# espism-v3.net
KiCad netlist of a schematic drawn in EAGLE
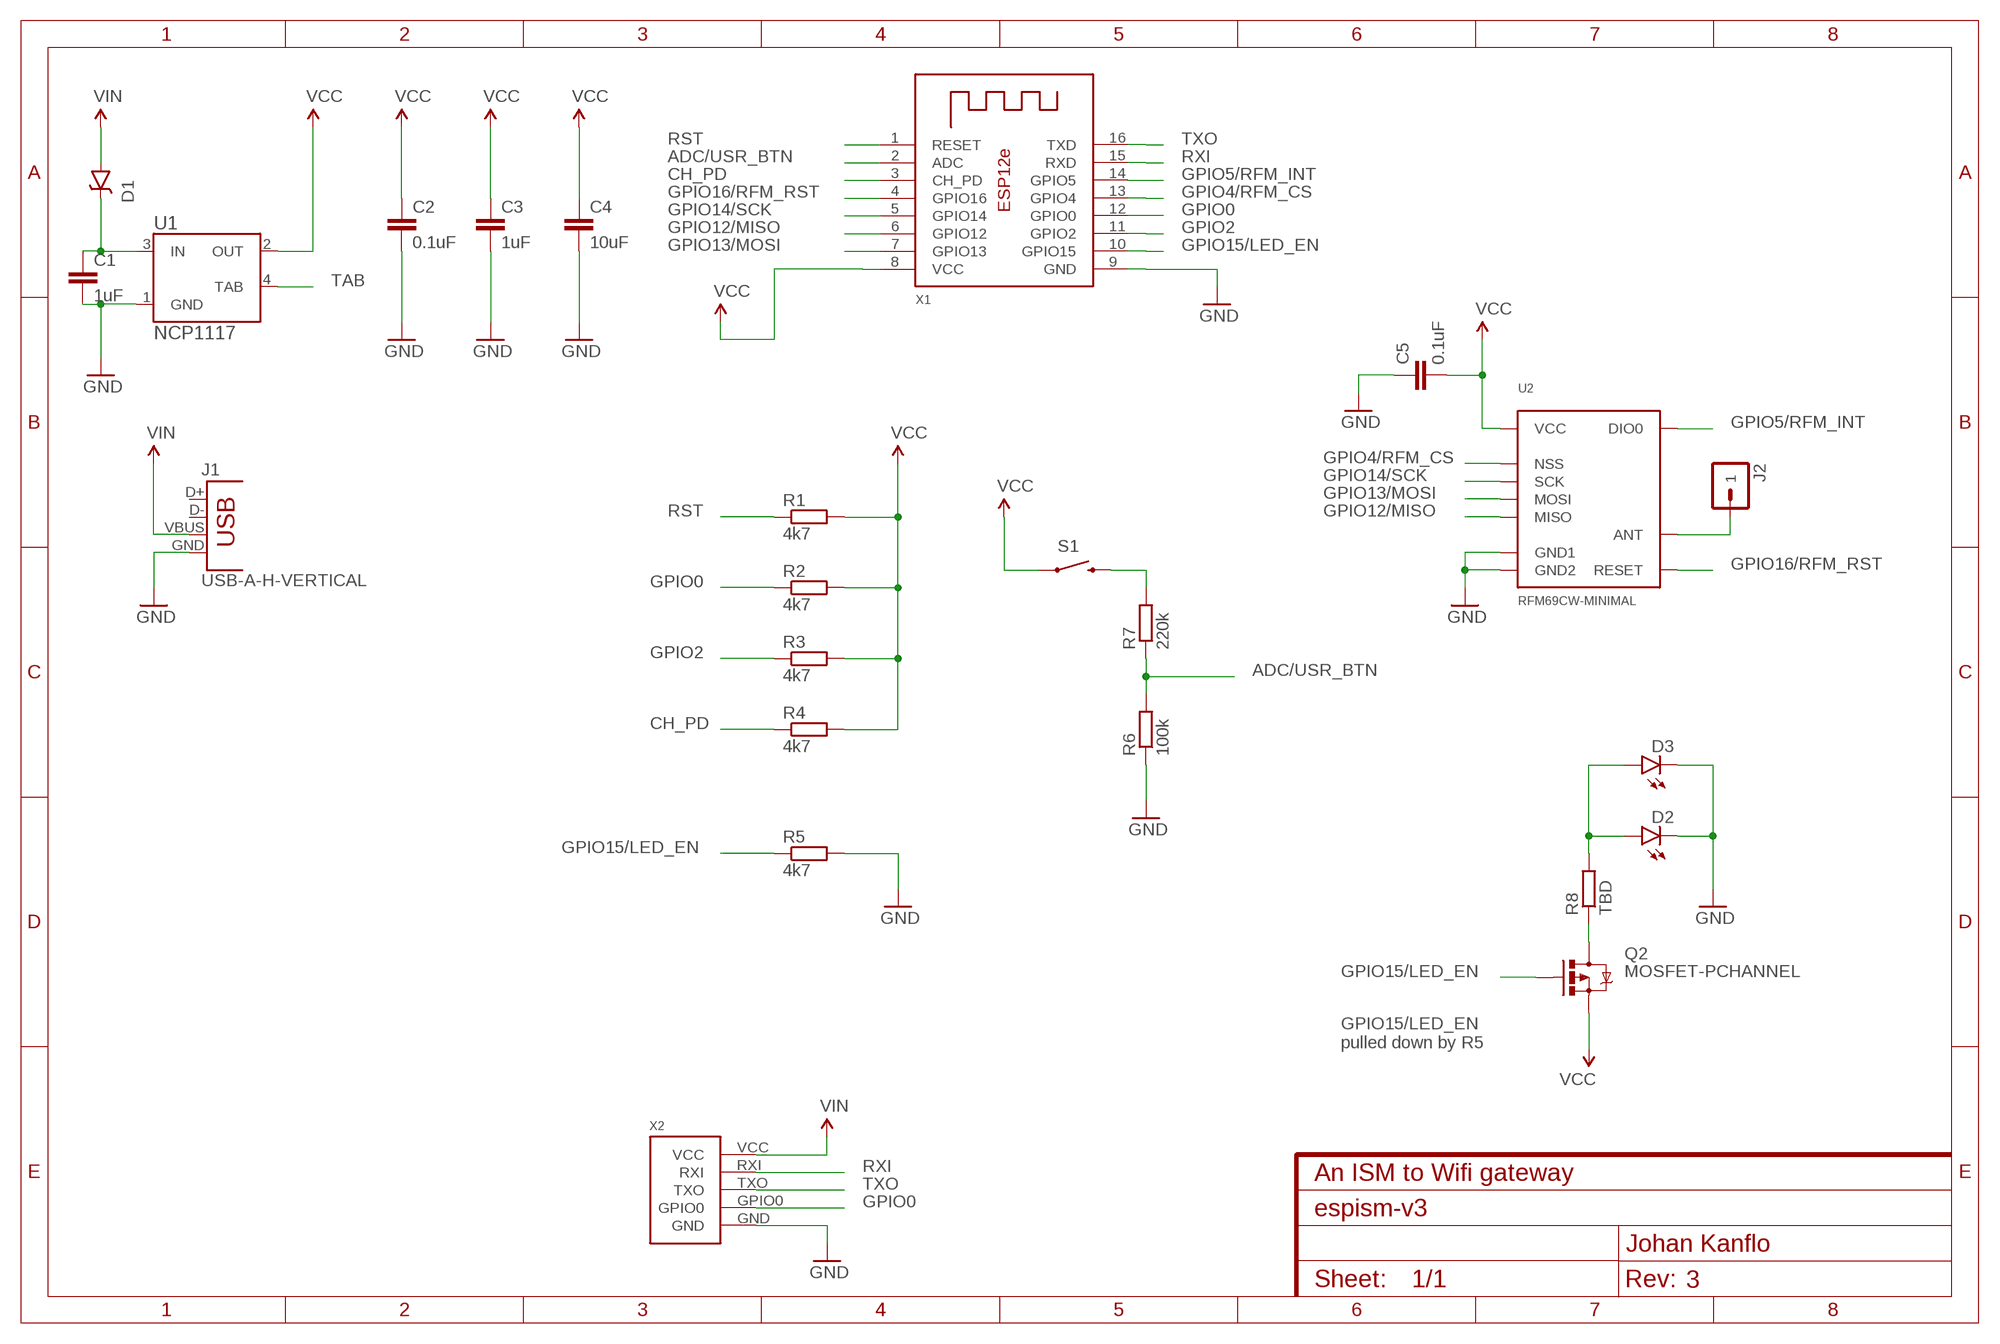
[diagram p0: schematic, sheet 1]

(export (version "E")
  (design (tool "Eeschema 10.0.6"))
  (components
    (comp (ref "C1")
      (value "1uF")
      (footprint "eagle-import:0603-CAP")
      (libsource (lib "eagle-import") (part "CAP0603-CAP"))
    )
    (comp (ref "C2")
      (value "0.1uF")
      (footprint "eagle-import:0603-CAP")
      (libsource (lib "eagle-import") (part "CAP0603-CAP"))
    )
    (comp (ref "C3")
      (value "1uF")
      (footprint "eagle-import:0603-CAP")
      (libsource (lib "eagle-import") (part "CAP0603-CAP"))
    )
    (comp (ref "C4")
      (value "10uF")
      (footprint "eagle-import:0603-CAP")
      (libsource (lib "eagle-import") (part "CAP0603-CAP"))
    )
    (comp (ref "C5")
      (value "0.1uF")
      (footprint "eagle-import:0603-CAP")
      (libsource (lib "eagle-import") (part "CAP0603-CAP"))
    )
    (comp (ref "D1")
      (value "DIODE-SCHOTTKYSOD-123FL")
      (footprint "eagle-import:SOD-123FL")
      (libsource (lib "eagle-import") (part "DIODE-SCHOTTKYSOD-123FL"))
    )
    (comp (ref "D2")
      (value "LED0603")
      (footprint "eagle-import:LED-0603")
      (libsource (lib "eagle-import") (part "LED0603"))
    )
    (comp (ref "D3")
      (value "LED0603")
      (footprint "eagle-import:LED-0603")
      (libsource (lib "eagle-import") (part "LED0603"))
    )
    (comp (ref "J1")
      (value "USB-A-H-VERTICAL")
      (footprint "eagle-import:USB-A-H-VERTICAL")
      (libsource (lib "eagle-import") (part "USB-A-H-VERTICAL"))
    )
    (comp (ref "J2")
      (value "M01-ANTENNA")
      (footprint "eagle-import:1X01-ANTENNA")
      (libsource (lib "eagle-import") (part "M01-ANTENNA"))
    )
    (comp (ref "Q2")
      (value "MOSFET-PCHANNEL")
      (footprint "eagle-import:SOT23-3")
      (libsource (lib "eagle-import") (part "MOSFET-PCHANNEL"))
    )
    (comp (ref "R1")
      (value "4k7")
      (footprint "eagle-import:R0603")
      (libsource (lib "eagle-import") (part "R-EU_R0603"))
    )
    (comp (ref "R2")
      (value "4k7")
      (footprint "eagle-import:R0603")
      (libsource (lib "eagle-import") (part "R-EU_R0603"))
    )
    (comp (ref "R3")
      (value "4k7")
      (footprint "eagle-import:R0603")
      (libsource (lib "eagle-import") (part "R-EU_R0603"))
    )
    (comp (ref "R4")
      (value "4k7")
      (footprint "eagle-import:R0603")
      (libsource (lib "eagle-import") (part "R-EU_R0603"))
    )
    (comp (ref "R5")
      (value "4k7")
      (footprint "eagle-import:R0603")
      (libsource (lib "eagle-import") (part "R-EU_R0603"))
    )
    (comp (ref "R6")
      (value "100k")
      (footprint "eagle-import:R0603")
      (libsource (lib "eagle-import") (part "R-EU_R0603"))
    )
    (comp (ref "R7")
      (value "220k")
      (footprint "eagle-import:R0603")
      (libsource (lib "eagle-import") (part "R-EU_R0603"))
    )
    (comp (ref "R8")
      (value "TBD")
      (footprint "eagle-import:R0603")
      (libsource (lib "eagle-import") (part "R-EU_R0603"))
    )
    (comp (ref "S1")
      (value "SWITCH-MOMENTARY-2SMD-1101NE")
      (footprint "eagle-import:TACTILE-SWITCH-1101NE")
      (libsource (lib "eagle-import") (part "SWITCH-MOMENTARY-2SMD-1101NE"))
    )
    (comp (ref "U1")
      (value "NCP1117")
      (footprint "eagle-import:SOT223")
      (libsource (lib "eagle-import") (part "NCP1117"))
    )
    (comp (ref "U2")
      (value "RFM69CW-MINIMAL")
      (footprint "eagle-import:RFM69CW-MINIMAL")
      (libsource (lib "eagle-import") (part "RFM69CW-MINIMAL"))
    )
    (comp (ref "X1")
      (value "ESP-12E")
      (footprint "eagle-import:ESP-12E")
      (libsource (lib "eagle-import") (part "ESP-12E"))
    )
    (comp (ref "X2")
      (value "ESPROGESPROG-DEVICE")
      (footprint "eagle-import:ESPROG")
      (libsource (lib "eagle-import") (part "ESPROGESPROG-DEVICE"))
    )
  )
  (nets
    (net (code "1") (name "/ADC{slash}USR_BTN") (class "Default")
      (node (ref "R6") (pin "2") (pinfunction "2_2") (pintype "passive"))
      (node (ref "R7") (pin "1") (pinfunction "1_1") (pintype "passive"))
      (node (ref "X1") (pin "2") (pinfunction "ADC_2") (pintype "passive"))
    )
    (net (code "2") (name "/CH_PD") (class "Default")
      (node (ref "R4") (pin "1") (pinfunction "1_1") (pintype "passive"))
      (node (ref "X1") (pin "3") (pinfunction "CH_PD_3") (pintype "input"))
    )
    (net (code "3") (name "/GPIO0") (class "Default")
      (node (ref "R2") (pin "1") (pinfunction "1_1") (pintype "passive"))
      (node (ref "X1") (pin "12") (pinfunction "GPIO0_12") (pintype "bidirectional"))
      (node (ref "X2") (pin "GPIO0") (pinfunction "GPIO0_GPIO0") (pintype "bidirectional"))
    )
    (net (code "4") (name "/GPIO2") (class "Default")
      (node (ref "R3") (pin "1") (pinfunction "1_1") (pintype "passive"))
      (node (ref "X1") (pin "11") (pinfunction "GPIO2_11") (pintype "bidirectional"))
    )
    (net (code "5") (name "/GPIO4{slash}RFM_CS") (class "Default")
      (node (ref "U2") (pin "NSS") (pinfunction "NSS_NSS") (pintype "input"))
      (node (ref "X1") (pin "13") (pinfunction "GPIO4_13") (pintype "bidirectional"))
    )
    (net (code "6") (name "/GPIO5{slash}RFM_INT") (class "Default")
      (node (ref "U2") (pin "DIO0") (pinfunction "DIO0_DIO0") (pintype "open_collector"))
      (node (ref "X1") (pin "14") (pinfunction "GPIO5_14") (pintype "bidirectional"))
    )
    (net (code "7") (name "/GPIO12{slash}MISO") (class "Default")
      (node (ref "U2") (pin "MISO") (pinfunction "MISO_MISO") (pintype "output"))
      (node (ref "X1") (pin "6") (pinfunction "GPIO12_6") (pintype "bidirectional"))
    )
    (net (code "8") (name "/GPIO13{slash}MOSI") (class "Default")
      (node (ref "U2") (pin "MOSI") (pinfunction "MOSI_MOSI") (pintype "input"))
      (node (ref "X1") (pin "7") (pinfunction "GPIO13_7") (pintype "bidirectional"))
    )
    (net (code "9") (name "/GPIO14{slash}SCK") (class "Default")
      (node (ref "U2") (pin "SCK") (pinfunction "SCK_SCK") (pintype "input"))
      (node (ref "X1") (pin "5") (pinfunction "GPIO14_5") (pintype "bidirectional"))
    )
    (net (code "10") (name "/GPIO15{slash}LED_EN") (class "Default")
      (node (ref "Q2") (pin "1") (pinfunction "G_1") (pintype "passive"))
      (node (ref "R5") (pin "1") (pinfunction "1_1") (pintype "passive"))
      (node (ref "X1") (pin "10") (pinfunction "GPIO15_10") (pintype "bidirectional"))
    )
    (net (code "11") (name "/GPIO16{slash}RFM_RST") (class "Default")
      (node (ref "U2") (pin "RESET") (pinfunction "RESET_RESET") (pintype "bidirectional"))
      (node (ref "X1") (pin "4") (pinfunction "GPIO16_4") (pintype "bidirectional"))
    )
    (net (code "12") (name "/RST") (class "Default")
      (node (ref "R1") (pin "1") (pinfunction "1_1") (pintype "passive"))
      (node (ref "X1") (pin "1") (pinfunction "RESET_1") (pintype "input"))
    )
    (net (code "13") (name "/RXI") (class "Default")
      (node (ref "X1") (pin "15") (pinfunction "RXD_15") (pintype "input"))
      (node (ref "X2") (pin "RXI") (pinfunction "RXI_RXI") (pintype "bidirectional"))
    )
    (net (code "14") (name "/TAB") (class "Default")
      (node (ref "U1") (pin "4") (pinfunction "TAB_4") (pintype "bidirectional"))
    )
    (net (code "15") (name "/TXO") (class "Default")
      (node (ref "X1") (pin "16") (pinfunction "TXD_16") (pintype "output"))
      (node (ref "X2") (pin "TXO") (pinfunction "TXO_TXO") (pintype "bidirectional"))
    )
    (net (code "16") (name "GND") (class "Default")
      (node (ref "C1") (pin "2") (pinfunction "2_2") (pintype "passive"))
      (node (ref "C2") (pin "2") (pinfunction "2_2") (pintype "passive"))
      (node (ref "C3") (pin "2") (pinfunction "2_2") (pintype "passive"))
      (node (ref "C4") (pin "2") (pinfunction "2_2") (pintype "passive"))
      (node (ref "C5") (pin "1") (pinfunction "1_1") (pintype "passive"))
      (node (ref "D2") (pin "C") (pinfunction "C_C") (pintype "passive"))
      (node (ref "D3") (pin "C") (pinfunction "C_C") (pintype "passive"))
      (node (ref "J1") (pin "GND") (pinfunction "GND_GND") (pintype "bidirectional"))
      (node (ref "R5") (pin "2") (pinfunction "2_2") (pintype "passive"))
      (node (ref "R6") (pin "1") (pinfunction "1_1") (pintype "passive"))
      (node (ref "U1") (pin "1") (pinfunction "GND_1") (pintype "bidirectional"))
      (node (ref "U2") (pin "GND@1") (pinfunction "GND1_GND@1") (pintype "power_in"))
      (node (ref "U2") (pin "GND@2") (pinfunction "GND2_GND@2") (pintype "power_in"))
      (node (ref "X1") (pin "9") (pinfunction "GND_9") (pintype "power_in"))
      (node (ref "X2") (pin "GND") (pinfunction "GND_GND") (pintype "bidirectional"))
    )
    (net (code "17") (name "Net-(D2-PadA)") (class "Default")
      (node (ref "D2") (pin "A") (pinfunction "A_A") (pintype "passive"))
      (node (ref "D3") (pin "A") (pinfunction "A_A") (pintype "passive"))
      (node (ref "R8") (pin "2") (pinfunction "2_2") (pintype "passive"))
    )
    (net (code "18") (name "Net-(J2-Pad1)") (class "Default")
      (node (ref "J2") (pin "1") (pinfunction "1_1") (pintype "bidirectional"))
      (node (ref "U2") (pin "ANT") (pinfunction "ANT_ANT") (pintype "passive"))
    )
    (net (code "19") (name "Net-(Q2-D)") (class "Default")
      (node (ref "Q2") (pin "3") (pinfunction "D_3") (pintype "passive"))
      (node (ref "R8") (pin "1") (pinfunction "1_1") (pintype "passive"))
    )
    (net (code "20") (name "Net-(R7-Pad2)") (class "Default")
      (node (ref "R7") (pin "2") (pinfunction "2_2") (pintype "passive"))
      (node (ref "S1") (pin "2") (pinfunction "2_2") (pintype "passive"))
    )
    (net (code "21") (name "Net-(U1-IN)") (class "Default")
      (node (ref "C1") (pin "1") (pinfunction "1_1") (pintype "passive"))
      (node (ref "D1") (pin "C") (pinfunction "C_C") (pintype "passive"))
      (node (ref "U1") (pin "3") (pinfunction "IN_3") (pintype "bidirectional"))
    )
    (net (code "22") (name "VCC") (class "Default")
      (node (ref "C2") (pin "1") (pinfunction "1_1") (pintype "passive"))
      (node (ref "C3") (pin "1") (pinfunction "1_1") (pintype "passive"))
      (node (ref "C4") (pin "1") (pinfunction "1_1") (pintype "passive"))
      (node (ref "C5") (pin "2") (pinfunction "2_2") (pintype "passive"))
      (node (ref "Q2") (pin "2") (pinfunction "S_2") (pintype "passive"))
      (node (ref "R1") (pin "2") (pinfunction "2_2") (pintype "passive"))
      (node (ref "R2") (pin "2") (pinfunction "2_2") (pintype "passive"))
      (node (ref "R3") (pin "2") (pinfunction "2_2") (pintype "passive"))
      (node (ref "R4") (pin "2") (pinfunction "2_2") (pintype "passive"))
      (node (ref "S1") (pin "1") (pinfunction "1_1") (pintype "passive"))
      (node (ref "U1") (pin "2") (pinfunction "OUT_2") (pintype "bidirectional"))
      (node (ref "U2") (pin "VDD") (pinfunction "VCC_VDD") (pintype "power_in"))
      (node (ref "X1") (pin "8") (pinfunction "VCC_8") (pintype "power_in"))
    )
    (net (code "23") (name "VIN") (class "Default")
      (node (ref "D1") (pin "A") (pinfunction "A_A") (pintype "passive"))
      (node (ref "J1") (pin "VBUS") (pinfunction "VBUS_VBUS") (pintype "bidirectional"))
      (node (ref "X2") (pin "VCC") (pinfunction "VCC_VCC") (pintype "bidirectional"))
    )
    (net (code "24") (name "unconnected-(J1-PadD+)") (class "Default")
      (node (ref "J1") (pin "D+") (pinfunction "D+_D+") (pintype "bidirectional"))
    )
    (net (code "25") (name "unconnected-(J1-PadD-)") (class "Default")
      (node (ref "J1") (pin "D-") (pinfunction "D-_D-") (pintype "bidirectional"))
    )
  )
)
